# Qwiic_Environmental_BME680.net
KiCad netlist of a schematic drawn in EAGLE
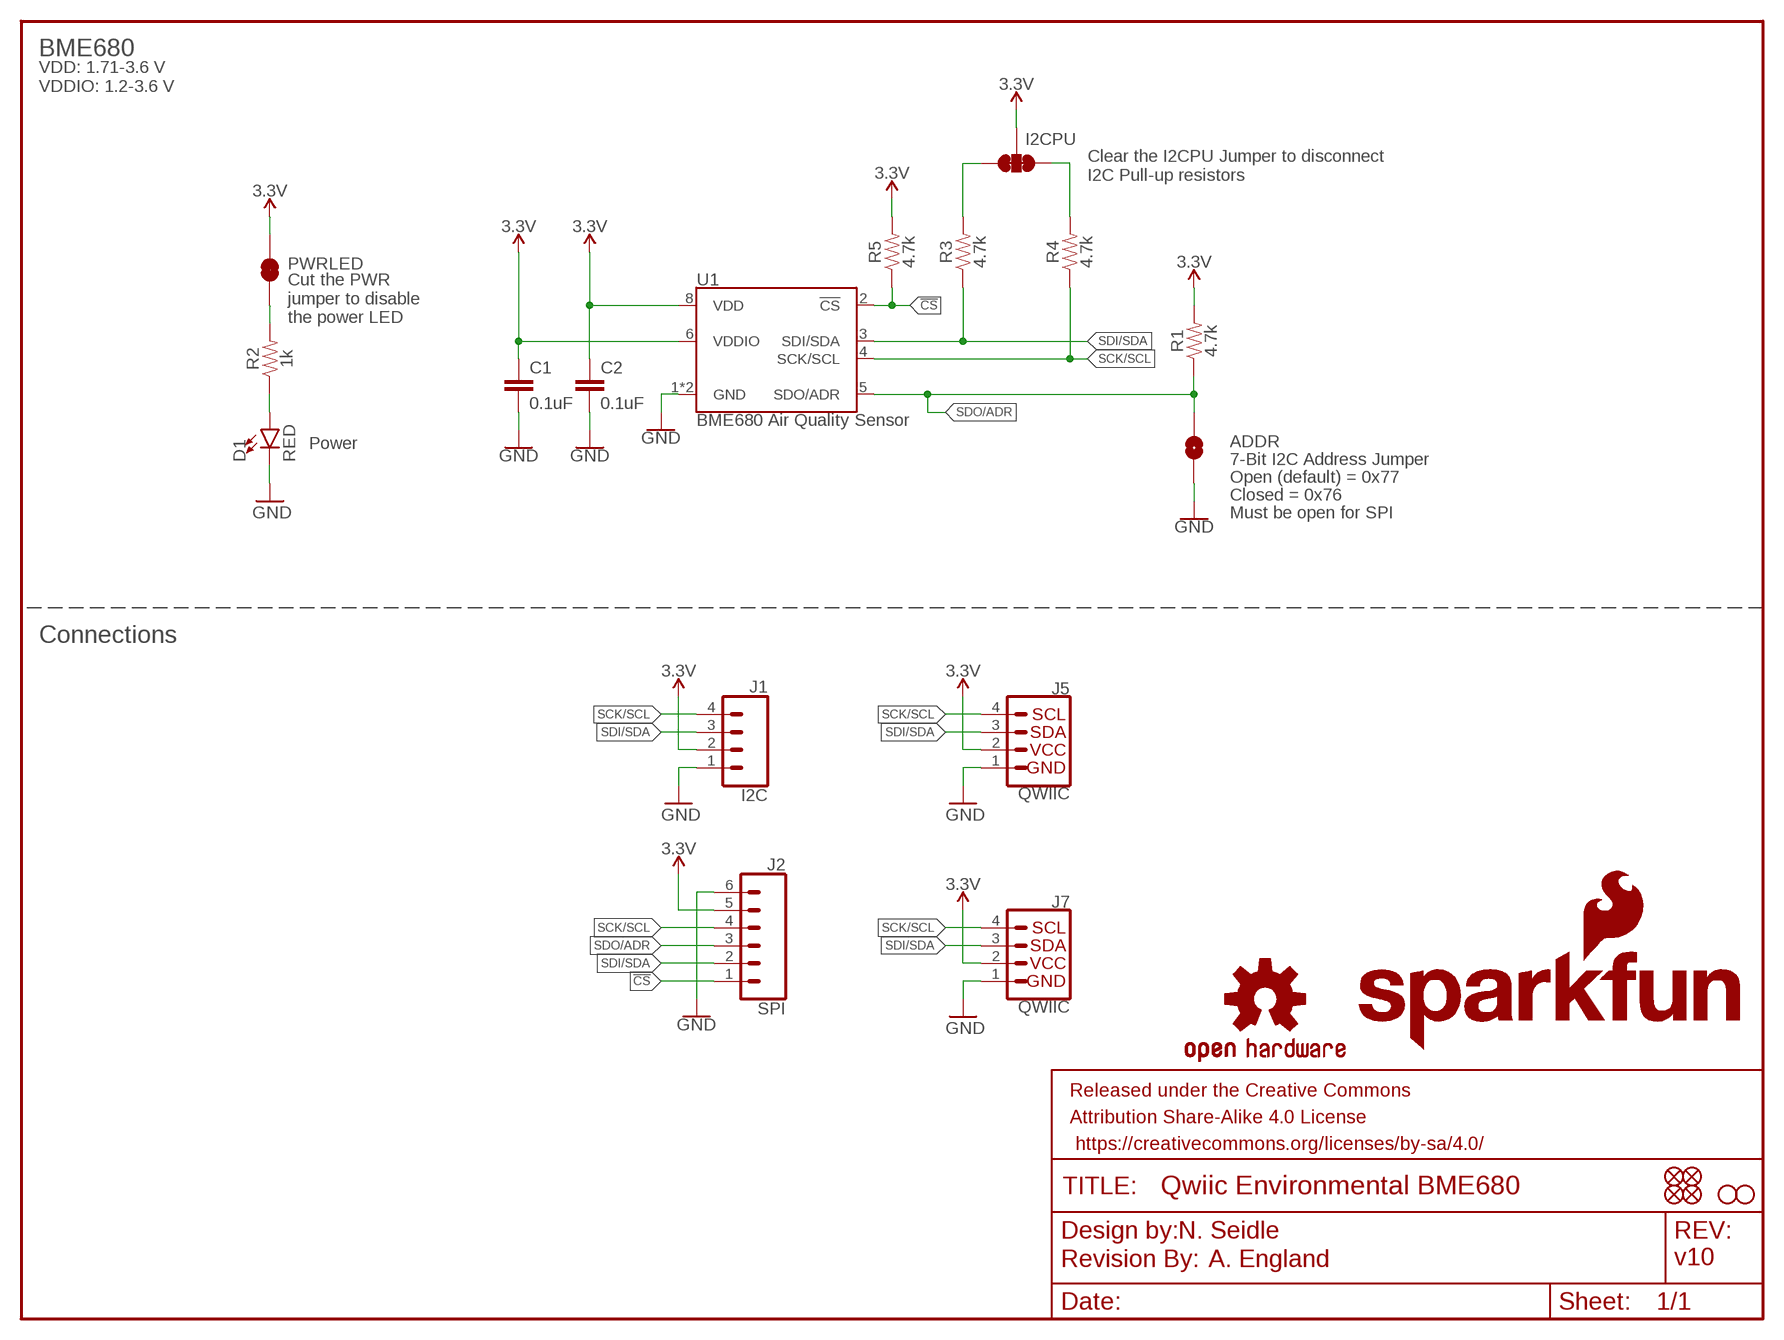
[diagram p0: schematic, sheet 1]

(export (version "E")
  (design (tool "Eeschema 10.0.6"))
  (components
    (comp (ref "ADDR")
      (value "JUMPER-SMT_2_NO_SILK")
      (footprint "eagle-import:SMT-JUMPER_2_NO_SILK")
      (libsource (lib "eagle-import") (part "JUMPER-SMT_2_NO_SILK"))
    )
    (comp (ref "C1")
      (value "0.1uF")
      (footprint "eagle-import:0603")
      (libsource (lib "eagle-import") (part "0.1UF-0603-100V-10%"))
    )
    (comp (ref "C2")
      (value "0.1uF")
      (footprint "eagle-import:0603")
      (libsource (lib "eagle-import") (part "0.1UF-0603-100V-10%"))
    )
    (comp (ref "D1")
      (value "RED")
      (footprint "eagle-import:LED-0603")
      (libsource (lib "eagle-import") (part "LED-RED0603"))
    )
    (comp (ref "FD1")
      (value "FIDUCIALUFIDUCIAL")
      (footprint "eagle-import:FIDUCIAL-MICRO")
      (libsource (lib "eagle-import") (part "FIDUCIALUFIDUCIAL"))
    )
    (comp (ref "FD2")
      (value "FIDUCIALUFIDUCIAL")
      (footprint "eagle-import:FIDUCIAL-MICRO")
      (libsource (lib "eagle-import") (part "FIDUCIALUFIDUCIAL"))
    )
    (comp (ref "FD3")
      (value "FIDUCIALUFIDUCIAL")
      (footprint "eagle-import:FIDUCIAL-MICRO")
      (libsource (lib "eagle-import") (part "FIDUCIALUFIDUCIAL"))
    )
    (comp (ref "FD4")
      (value "FIDUCIALUFIDUCIAL")
      (footprint "eagle-import:FIDUCIAL-MICRO")
      (libsource (lib "eagle-import") (part "FIDUCIALUFIDUCIAL"))
    )
    (comp (ref "FRAME1")
      (value "FRAME-LETTER")
      (footprint "eagle-import:CREATIVE_COMMONS")
      (libsource (lib "eagle-import") (part "FRAME-LETTER"))
    )
    (comp (ref "H1")
      (value "STAND-OFFTIGHT")
      (footprint "eagle-import:STAND-OFF-TIGHT")
      (libsource (lib "eagle-import") (part "STAND-OFFTIGHT"))
    )
    (comp (ref "H2")
      (value "STAND-OFFTIGHT")
      (footprint "eagle-import:STAND-OFF-TIGHT")
      (libsource (lib "eagle-import") (part "STAND-OFFTIGHT"))
    )
    (comp (ref "I2CPU")
      (value "I2C PU")
      (footprint "eagle-import:SMT-JUMPER_3_2-NC_TRACE_SILK")
      (libsource (lib "eagle-import") (part "JUMPER-SMT_3_2-NC_TRACE_SILK"))
    )
    (comp (ref "J1")
      (value "I2C")
      (footprint "eagle-import:1X04_NO_SILK")
      (libsource (lib "eagle-import") (part "CONN_041X04_NO_SILK"))
    )
    (comp (ref "J2")
      (value "SPI")
      (footprint "eagle-import:1X06_NO_SILK")
      (libsource (lib "eagle-import") (part "CONN_06NO_SILK_FEMALE_PTH"))
    )
    (comp (ref "J5")
      (value "QWIIC")
      (footprint "eagle-import:JST04_1MM_RA")
      (libsource (lib "eagle-import") (part "QWIIC_CONNECTORJS-1MM"))
    )
    (comp (ref "J7")
      (value "QWIIC")
      (footprint "eagle-import:JST04_1MM_RA")
      (libsource (lib "eagle-import") (part "QWIIC_CONNECTORJS-1MM"))
    )
    (comp (ref "LOGO1")
      (value "OSHW-LOGOMINI")
      (footprint "eagle-import:OSHW-LOGO-MINI")
      (libsource (lib "eagle-import") (part "OSHW-LOGOMINI"))
    )
    (comp (ref "LOGO2")
      (value "SFE_LOGO_NAME_FLAME.1_INCH")
      (footprint "eagle-import:SFE_LOGO_NAME_FLAME_.1")
      (libsource (lib "eagle-import") (part "SFE_LOGO_NAME_FLAME.1_INCH"))
    )
    (comp (ref "LOGO3")
      (value "REVISION")
      (footprint "eagle-import:REVISION")
      (libsource (lib "eagle-import") (part "REVISION"))
    )
    (comp (ref "LOGO4")
      (value "SFE_LOGO_FLAME.1_INCH")
      (footprint "eagle-import:SFE_LOGO_FLAME_.1")
      (libsource (lib "eagle-import") (part "SFE_LOGO_FLAME.1_INCH"))
    )
    (comp (ref "PWRLED")
      (value "JUMPER-SMT_2_NC_TRACE_SILK")
      (footprint "eagle-import:SMT-JUMPER_2_NC_TRACE_SILK")
      (libsource (lib "eagle-import") (part "JUMPER-SMT_2_NC_TRACE_SILK"))
    )
    (comp (ref "R1")
      (value "4.7k")
      (footprint "eagle-import:0603@1")
      (libsource (lib "eagle-import") (part "4.7KOHM-0603-1/10W-1%"))
    )
    (comp (ref "R2")
      (value "1k")
      (footprint "eagle-import:0603")
      (libsource (lib "eagle-import") (part "1KOHM-0603-1/10W-1%"))
    )
    (comp (ref "R3")
      (value "4.7k")
      (footprint "eagle-import:0603@1")
      (libsource (lib "eagle-import") (part "4.7KOHM-0603-1/10W-1%"))
    )
    (comp (ref "R4")
      (value "4.7k")
      (footprint "eagle-import:0603@1")
      (libsource (lib "eagle-import") (part "4.7KOHM-0603-1/10W-1%"))
    )
    (comp (ref "R5")
      (value "4.7k")
      (footprint "eagle-import:0603@1")
      (libsource (lib "eagle-import") (part "4.7KOHM-0603-1/10W-1%"))
    )
    (comp (ref "U1")
      (value "BME680 Air Quality Sensor")
      (footprint "eagle-import:LGA3.0X3.0")
      (libsource (lib "eagle-import") (part "BME680-LGA"))
    )
  )
  (nets
    (net (code "1") (name "/~{CS}") (class "Default")
      (node (ref "J2") (pin "1") (pinfunction "1_1") (pintype "passive"))
      (node (ref "R5") (pin "1") (pinfunction "1_1") (pintype "passive"))
      (node (ref "U1") (pin "2") (pinfunction "~{CS}_2") (pintype "bidirectional"))
    )
    (net (code "2") (name "3.3V") (class "Default")
      (node (ref "C1") (pin "1") (pinfunction "1_1") (pintype "passive"))
      (node (ref "C2") (pin "1") (pinfunction "1_1") (pintype "passive"))
      (node (ref "I2CPU") (pin "2") (pinfunction "2_2") (pintype "passive"))
      (node (ref "J1") (pin "2") (pinfunction "2_2") (pintype "passive"))
      (node (ref "J2") (pin "5") (pinfunction "5_5") (pintype "passive"))
      (node (ref "J5") (pin "2") (pinfunction "2_2") (pintype "power_in"))
      (node (ref "J7") (pin "2") (pinfunction "2_2") (pintype "power_in"))
      (node (ref "PWRLED") (pin "2") (pinfunction "2_2") (pintype "passive"))
      (node (ref "R1") (pin "2") (pinfunction "2_2") (pintype "passive"))
      (node (ref "R5") (pin "2") (pinfunction "2_2") (pintype "passive"))
      (node (ref "U1") (pin "6") (pinfunction "VDDIO_6") (pintype "bidirectional"))
      (node (ref "U1") (pin "8") (pinfunction "VDD_8") (pintype "bidirectional"))
    )
    (net (code "3") (name "GND") (class "Default")
      (node (ref "ADDR") (pin "1") (pinfunction "1_1") (pintype "passive"))
      (node (ref "C1") (pin "2") (pinfunction "2_2") (pintype "passive"))
      (node (ref "C2") (pin "2") (pinfunction "2_2") (pintype "passive"))
      (node (ref "D1") (pin "C") (pinfunction "C_C") (pintype "passive"))
      (node (ref "J1") (pin "1") (pinfunction "1_1") (pintype "passive"))
      (node (ref "J2") (pin "6") (pinfunction "6_6") (pintype "passive"))
      (node (ref "J5") (pin "1") (pinfunction "1_1") (pintype "power_in"))
      (node (ref "J7") (pin "1") (pinfunction "1_1") (pintype "power_in"))
      (node (ref "U1") (pin "1") (pinfunction "GND_1") (pintype "bidirectional"))
      (node (ref "U1") (pin "7") (pinfunction "GND_7") (pintype "bidirectional"))
    )
    (net (code "4") (name "Net-(D1-PadA)") (class "Default")
      (node (ref "D1") (pin "A") (pinfunction "A_A") (pintype "passive"))
      (node (ref "R2") (pin "1") (pinfunction "1_1") (pintype "passive"))
    )
    (net (code "5") (name "Net-(I2CPU-Pad1)") (class "Default")
      (node (ref "I2CPU") (pin "1") (pinfunction "1_1") (pintype "passive"))
      (node (ref "R4") (pin "2") (pinfunction "2_2") (pintype "passive"))
    )
    (net (code "6") (name "Net-(I2CPU-Pad3)") (class "Default")
      (node (ref "I2CPU") (pin "3") (pinfunction "3_3") (pintype "passive"))
      (node (ref "R3") (pin "2") (pinfunction "2_2") (pintype "passive"))
    )
    (net (code "7") (name "Net-(PWRLED-Pad1)") (class "Default")
      (node (ref "PWRLED") (pin "1") (pinfunction "1_1") (pintype "passive"))
      (node (ref "R2") (pin "2") (pinfunction "2_2") (pintype "passive"))
    )
    (net (code "8") (name "SCK{slash}SCL") (class "Default")
      (node (ref "J1") (pin "4") (pinfunction "4_4") (pintype "passive"))
      (node (ref "J2") (pin "4") (pinfunction "4_4") (pintype "passive"))
      (node (ref "J5") (pin "4") (pinfunction "4_4") (pintype "passive"))
      (node (ref "J7") (pin "4") (pinfunction "4_4") (pintype "passive"))
      (node (ref "R4") (pin "1") (pinfunction "1_1") (pintype "passive"))
      (node (ref "U1") (pin "4") (pinfunction "SCK/SCL_4") (pintype "bidirectional"))
    )
    (net (code "9") (name "SDI{slash}SDA") (class "Default")
      (node (ref "J1") (pin "3") (pinfunction "3_3") (pintype "passive"))
      (node (ref "J2") (pin "2") (pinfunction "2_2") (pintype "passive"))
      (node (ref "J5") (pin "3") (pinfunction "3_3") (pintype "passive"))
      (node (ref "J7") (pin "3") (pinfunction "3_3") (pintype "passive"))
      (node (ref "R3") (pin "1") (pinfunction "1_1") (pintype "passive"))
      (node (ref "U1") (pin "3") (pinfunction "SDI/SDA_3") (pintype "bidirectional"))
    )
    (net (code "10") (name "SDO{slash}ADR") (class "Default")
      (node (ref "ADDR") (pin "2") (pinfunction "2_2") (pintype "passive"))
      (node (ref "J2") (pin "3") (pinfunction "3_3") (pintype "passive"))
      (node (ref "R1") (pin "1") (pinfunction "1_1") (pintype "passive"))
      (node (ref "U1") (pin "5") (pinfunction "SDO/ADR_5") (pintype "bidirectional"))
    )
  )
)
